# IHM.net
KiCad netlist of a schematic drawn in Altium Designer
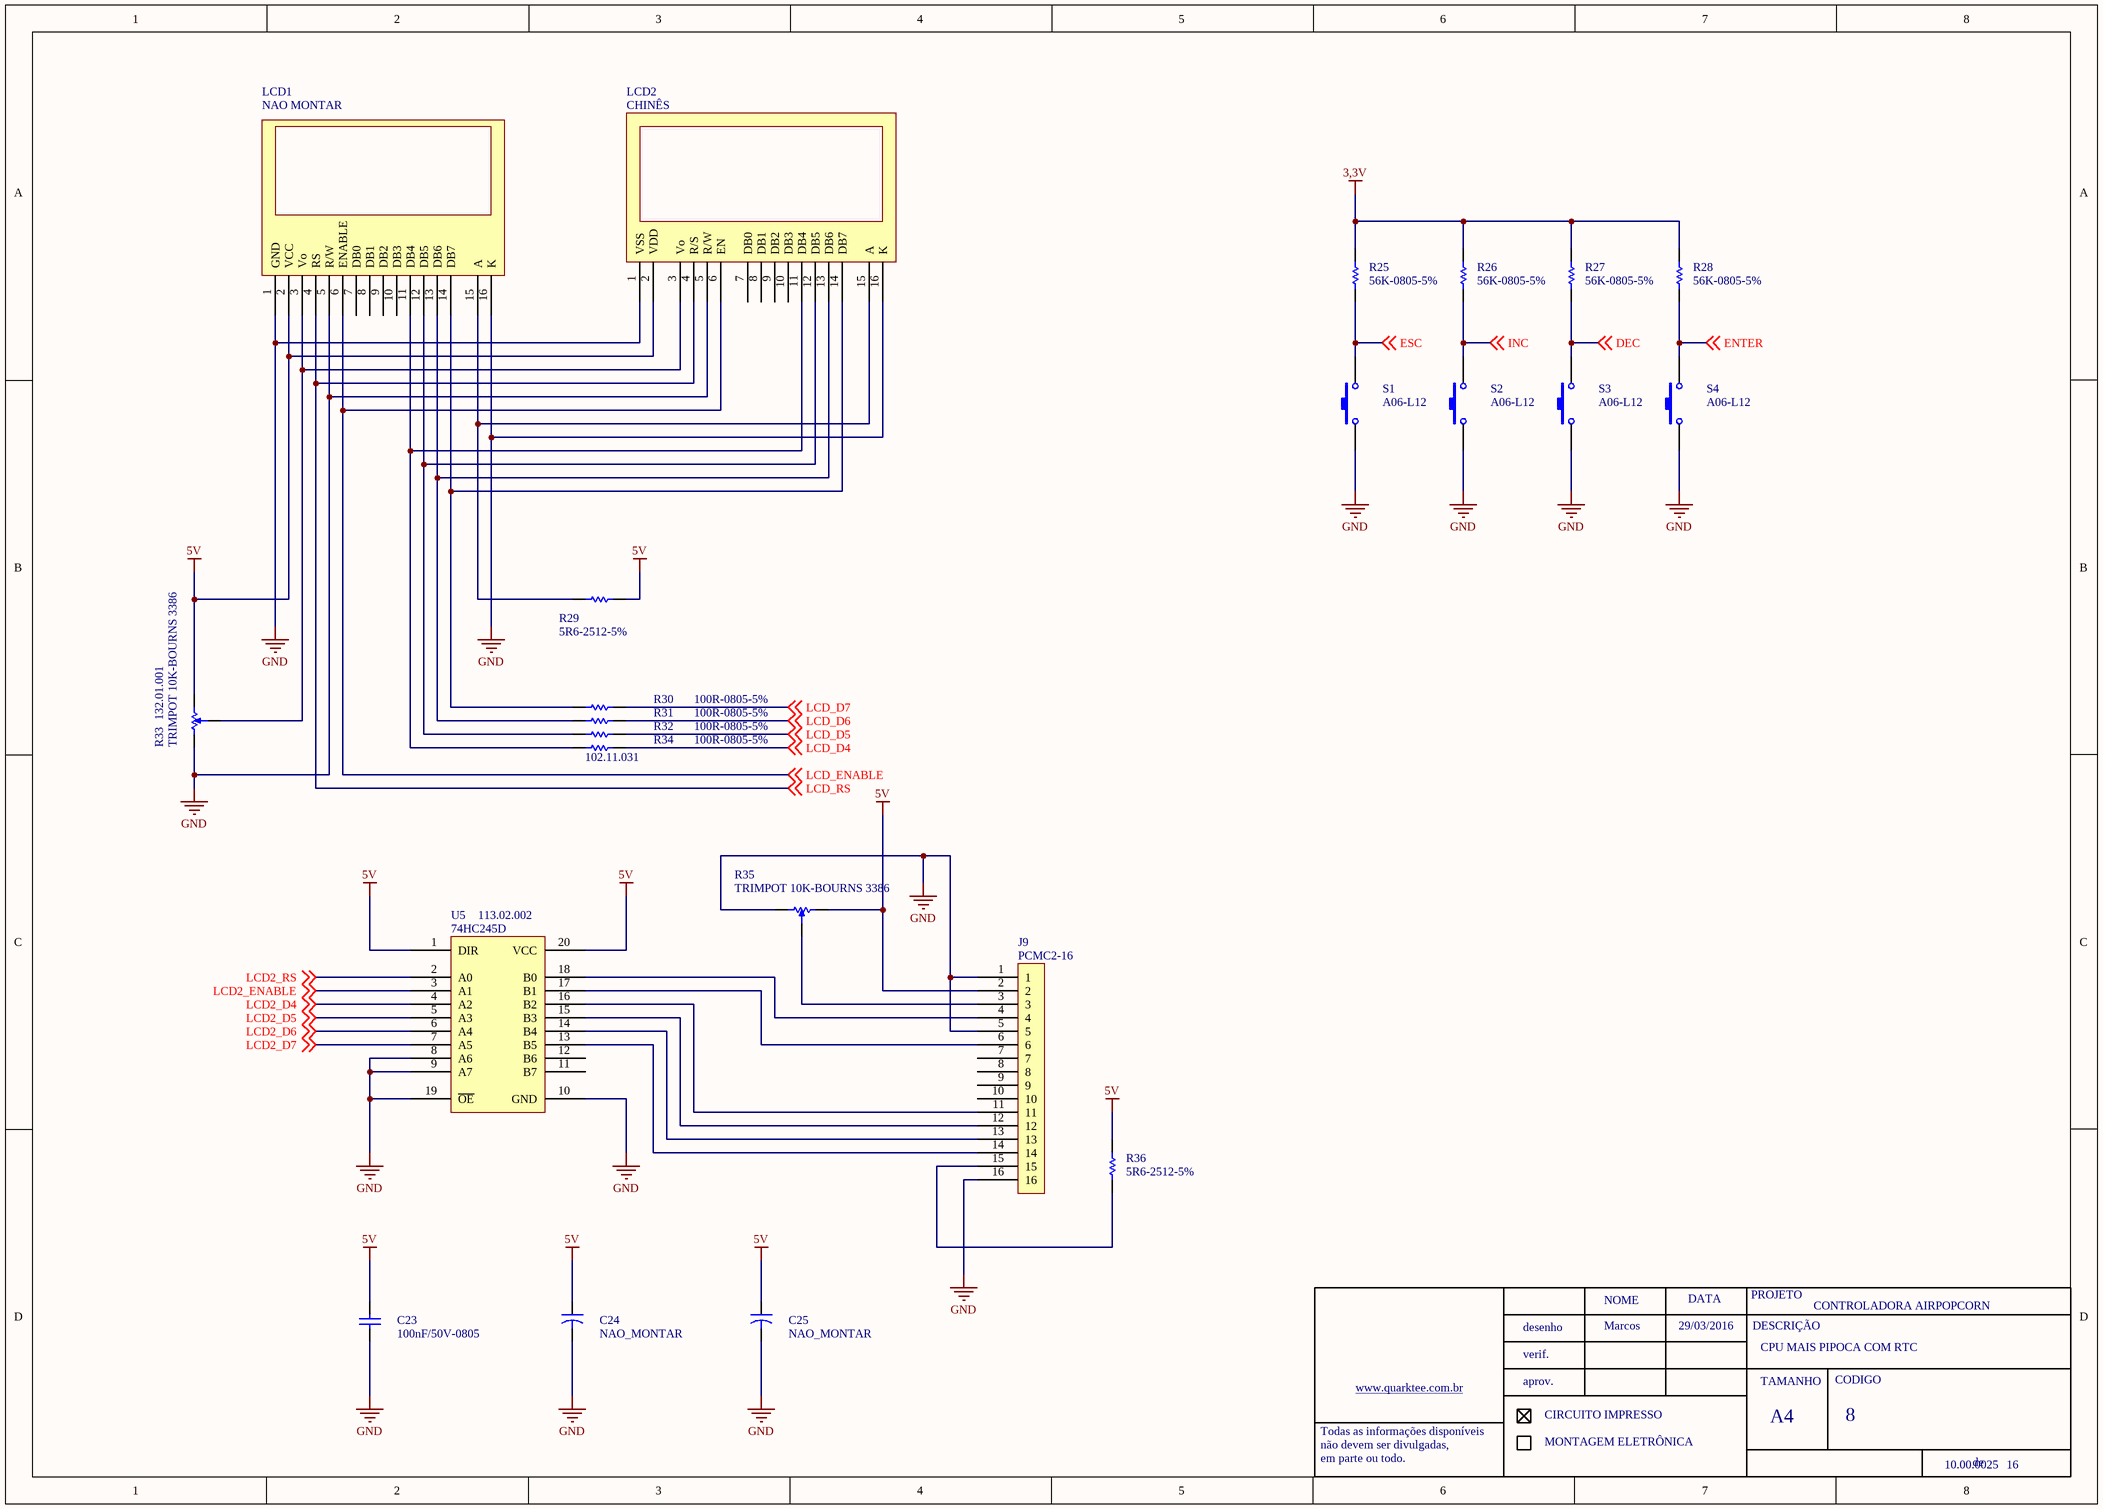
[diagram p0: IHM.SchDoc]

(export (version "E")
  (design (tool "Eeschema 10.0.6"))
  (components
    (comp (ref "C23")
      (value "100nF/50V-0805")
      (footprint "0805-REVISADO O")
      (description "100nF/50-0805-NPO")
      (libsource (lib "AquinoLib") (part "100nF/50-0805-NPO"))
    )
    (comp (ref "C24")
      (value "NAO_MONTAR")
      (footprint "CAP 2413 POLARI")
      (description "10uF/35V-tantalo")
      (libsource (lib "AquinoLib") (part "10uF/35V-tantalo"))
    )
    (comp (ref "C25")
      (value "NAO_MONTAR")
      (footprint "CAP 2413 POLARI")
      (description "10uF/35V-tantalo")
      (libsource (lib "AquinoLib") (part "10uF/35V-tantalo"))
    )
    (comp (ref "J9")
      (value "PCMC2-16")
      (footprint "PCMC2-16")
      (libsource (lib "AquinoLib") (part "PCMC2-16"))
    )
    (comp (ref "LCD1")
      (value "NAO MONTAR")
      (footprint "WH1602_WH1602(Primary)")
      (description "WH1602A")
      (libsource (lib "ChaveDigital3") (part "WH1602A"))
    )
    (comp (ref "LCD2")
      (value "CHINÊS")
      (footprint "LCD CHINES_LCD_CHINES(Primary)")
      (description "WH2002")
      (libsource (lib "ChaveDigital3") (part "WH2002"))
    )
    (comp (ref "R25")
      (value "56K-0805-5%")
      (footprint "0805-REVISADO O")
      (libsource (lib "AquinoLib") (part "56K-0805-5%"))
    )
    (comp (ref "R26")
      (value "56K-0805-5%")
      (footprint "0805-REVISADO O")
      (libsource (lib "AquinoLib") (part "56K-0805-5%"))
    )
    (comp (ref "R27")
      (value "56K-0805-5%")
      (footprint "0805-REVISADO O")
      (libsource (lib "AquinoLib") (part "56K-0805-5%"))
    )
    (comp (ref "R28")
      (value "56K-0805-5%")
      (footprint "0805-REVISADO O")
      (libsource (lib "AquinoLib") (part "56K-0805-5%"))
    )
    (comp (ref "R29")
      (value "5R6-2512-5%")
      (footprint "2512 - REVISADO")
      (description "5R6-CR100")
      (libsource (lib "ChaveDigital3") (part "RES 5R6-CR100"))
    )
    (comp (ref "R30")
      (value "100R-0805-5%")
      (footprint "0805-REVISADO O")
      (libsource (lib "AquinoLib") (part "100R-0805-5%"))
    )
    (comp (ref "R31")
      (value "100R-0805-5%")
      (footprint "0805-REVISADO O")
      (libsource (lib "AquinoLib") (part "100R-0805-5%"))
    )
    (comp (ref "R32")
      (value "100R-0805-5%")
      (footprint "0805-REVISADO O")
      (fields (field (name "ERP") "102.11.031"))
      (libsource (lib "AquinoLib") (part "100R-0805-5%"))
    )
    (comp (ref "R33")
      (value "TRIMPOT 10K-BOURNS 3386")
      (footprint "TRIMPOT 3386")
      (fields (field (name "ERP") "132.01.001"))
      (libsource (lib "ChaveDigital3") (part "TRIMPOT 3386 50K"))
    )
    (comp (ref "R34")
      (value "100R-0805-5%")
      (footprint "0805-REVISADO O")
      (libsource (lib "AquinoLib") (part "100R-0805-5%"))
    )
    (comp (ref "R35")
      (value "TRIMPOT 10K-BOURNS 3386")
      (footprint "TRIMPOT 3386")
      (description "TRIMPOT 100K-0805-5%")
      (libsource (lib "AquinoLib") (part "TRIMPOT 10K-3386"))
    )
    (comp (ref "R36")
      (value "5R6-2512-5%")
      (footprint "2512 - REVISADO")
      (description "5R6-CR100")
      (libsource (lib "ChaveDigital3") (part "RES 5R6-CR100"))
    )
    (comp (ref "S1")
      (value "A06-L12")
      (footprint "CHAVE TACTIL NO_[125](Primary)")
      (libsource (lib "ChaveDigital3") (part "A06-L12"))
    )
    (comp (ref "S2")
      (value "A06-L12")
      (footprint "CHAVE TACTIL NO_[125](Primary)")
      (libsource (lib "ChaveDigital3") (part "A06-L12"))
    )
    (comp (ref "S3")
      (value "A06-L12")
      (footprint "CHAVE TACTIL NO_[125](Primary)")
      (libsource (lib "ChaveDigital3") (part "A06-L12"))
    )
    (comp (ref "S4")
      (value "A06-L12")
      (footprint "CHAVE TACTIL NO_[125](Primary)")
      (libsource (lib "ChaveDigital3") (part "A06-L12"))
    )
    (comp (ref "U5")
      (value "74HC245D")
      (footprint "SOIC 20 FEITO A")
      (fields (field (name "ERP") "113.02.002"))
      (libsource (lib "ChaveDigital3") (part "74HC245D"))
    )
  )
  (nets
    (net (code "1") (name "3,3V") (class "Default")
      (node (ref "R25") (pin "1") (pinfunction "1_1") (pintype "passive"))
      (node (ref "R26") (pin "1") (pinfunction "1_1") (pintype "passive"))
      (node (ref "R27") (pin "1") (pinfunction "1_1") (pintype "passive"))
      (node (ref "R28") (pin "1") (pinfunction "1_1") (pintype "passive"))
    )
    (net (code "2") (name "5V") (class "Default")
      (node (ref "C23") (pin "2") (pinfunction "2_2") (pintype "passive"))
      (node (ref "C24") (pin "1") (pinfunction "1_1") (pintype "passive"))
      (node (ref "C25") (pin "1") (pinfunction "1_1") (pintype "passive"))
      (node (ref "J9") (pin "2") (pinfunction "2_2") (pintype "passive"))
      (node (ref "LCD1") (pin "2") (pinfunction "VCC_2") (pintype "passive"))
      (node (ref "LCD2") (pin "2") (pinfunction "VDD_2") (pintype "passive"))
      (node (ref "R29") (pin "1") (pinfunction "1_1") (pintype "passive"))
      (node (ref "R33") (pin "1") (pinfunction "1_1") (pintype "passive"))
      (node (ref "R35") (pin "1") (pinfunction "1_1") (pintype "passive"))
      (node (ref "R36") (pin "2") (pinfunction "2_2") (pintype "passive"))
      (node (ref "U5") (pin "1") (pinfunction "DIR_1") (pintype "passive"))
      (node (ref "U5") (pin "20") (pinfunction "VCC_20") (pintype "passive"))
    )
    (net (code "3") (name "DEC") (class "Default")
      (node (ref "R27") (pin "2") (pinfunction "2_2") (pintype "passive"))
      (node (ref "S3") (pin "2") (pinfunction "2_2") (pintype "passive"))
    )
    (net (code "4") (name "ENTER") (class "Default")
      (node (ref "R28") (pin "2") (pinfunction "2_2") (pintype "passive"))
      (node (ref "S4") (pin "2") (pinfunction "2_2") (pintype "passive"))
    )
    (net (code "5") (name "ESC") (class "Default")
      (node (ref "R25") (pin "2") (pinfunction "2_2") (pintype "passive"))
      (node (ref "S1") (pin "2") (pinfunction "2_2") (pintype "passive"))
    )
    (net (code "6") (name "GND") (class "Default")
      (node (ref "C23") (pin "1") (pinfunction "1_1") (pintype "passive"))
      (node (ref "C24") (pin "2") (pinfunction "2_2") (pintype "passive"))
      (node (ref "C25") (pin "2") (pinfunction "2_2") (pintype "passive"))
      (node (ref "J9") (pin "1") (pinfunction "1_1") (pintype "passive"))
      (node (ref "J9") (pin "16") (pinfunction "16_16") (pintype "passive"))
      (node (ref "J9") (pin "5") (pinfunction "5_5") (pintype "passive"))
      (node (ref "LCD1") (pin "1") (pinfunction "GND_1") (pintype "passive"))
      (node (ref "LCD1") (pin "16") (pinfunction "K_16") (pintype "passive"))
      (node (ref "LCD1") (pin "5") (pinfunction "R/W_5") (pintype "passive"))
      (node (ref "LCD2") (pin "1") (pinfunction "VSS_1") (pintype "passive"))
      (node (ref "LCD2") (pin "16") (pinfunction "K_16") (pintype "passive"))
      (node (ref "LCD2") (pin "5") (pinfunction "R/W_5") (pintype "passive"))
      (node (ref "R33") (pin "3") (pinfunction "3_3") (pintype "passive"))
      (node (ref "R35") (pin "3") (pinfunction "3_3") (pintype "passive"))
      (node (ref "S1") (pin "1") (pinfunction "1_1") (pintype "passive"))
      (node (ref "S2") (pin "1") (pinfunction "1_1") (pintype "passive"))
      (node (ref "S3") (pin "1") (pinfunction "1_1") (pintype "passive"))
      (node (ref "S4") (pin "1") (pinfunction "1_1") (pintype "passive"))
      (node (ref "U5") (pin "10") (pinfunction "GND_10") (pintype "passive"))
      (node (ref "U5") (pin "19") (pinfunction "~{OE}_19") (pintype "passive"))
      (node (ref "U5") (pin "8") (pinfunction "A6_8") (pintype "passive"))
      (node (ref "U5") (pin "9") (pinfunction "A7_9") (pintype "passive"))
    )
    (net (code "7") (name "INC") (class "Default")
      (node (ref "R26") (pin "2") (pinfunction "2_2") (pintype "passive"))
      (node (ref "S2") (pin "2") (pinfunction "2_2") (pintype "passive"))
    )
    (net (code "8") (name "LCD2_D4") (class "Default")
      (node (ref "U5") (pin "4") (pinfunction "A2_4") (pintype "passive"))
    )
    (net (code "9") (name "LCD2_D5") (class "Default")
      (node (ref "U5") (pin "5") (pinfunction "A3_5") (pintype "passive"))
    )
    (net (code "10") (name "LCD2_D6") (class "Default")
      (node (ref "U5") (pin "6") (pinfunction "A4_6") (pintype "passive"))
    )
    (net (code "11") (name "LCD2_D7") (class "Default")
      (node (ref "U5") (pin "7") (pinfunction "A5_7") (pintype "passive"))
    )
    (net (code "12") (name "LCD2_ENABLE") (class "Default")
      (node (ref "U5") (pin "3") (pinfunction "A1_3") (pintype "passive"))
    )
    (net (code "13") (name "LCD2_RS") (class "Default")
      (node (ref "U5") (pin "2") (pinfunction "A0_2") (pintype "passive"))
    )
    (net (code "14") (name "LCD_D4") (class "Default")
      (node (ref "R34") (pin "2") (pinfunction "2_2") (pintype "passive"))
    )
    (net (code "15") (name "LCD_D5") (class "Default")
      (node (ref "R32") (pin "2") (pinfunction "2_2") (pintype "passive"))
    )
    (net (code "16") (name "LCD_D6") (class "Default")
      (node (ref "R31") (pin "2") (pinfunction "2_2") (pintype "passive"))
    )
    (net (code "17") (name "LCD_D7") (class "Default")
      (node (ref "R30") (pin "2") (pinfunction "2_2") (pintype "passive"))
    )
    (net (code "18") (name "LCD_ENABLE") (class "Default")
      (node (ref "LCD1") (pin "6") (pinfunction "ENABLE_6") (pintype "passive"))
      (node (ref "LCD2") (pin "6") (pinfunction "EN_6") (pintype "passive"))
    )
    (net (code "19") (name "LCD_RS") (class "Default")
      (node (ref "LCD1") (pin "4") (pinfunction "RS_4") (pintype "passive"))
      (node (ref "LCD2") (pin "4") (pinfunction "R/S_4") (pintype "passive"))
    )
    (net (code "20") (name "Net-(J9-Pad3)") (class "Default")
      (node (ref "J9") (pin "3") (pinfunction "3_3") (pintype "passive"))
      (node (ref "R35") (pin "2") (pinfunction "2_2") (pintype "passive"))
    )
    (net (code "21") (name "Net-(J9-Pad15)") (class "Default")
      (node (ref "J9") (pin "15") (pinfunction "15_15") (pintype "passive"))
      (node (ref "R36") (pin "1") (pinfunction "1_1") (pintype "passive"))
    )
    (net (code "22") (name "Net-(LCD1-A)") (class "Default")
      (node (ref "LCD1") (pin "15") (pinfunction "A_15") (pintype "passive"))
      (node (ref "LCD2") (pin "15") (pinfunction "A_15") (pintype "passive"))
      (node (ref "R29") (pin "2") (pinfunction "2_2") (pintype "passive"))
    )
    (net (code "23") (name "Net-(LCD1-DB4)") (class "Default")
      (node (ref "LCD1") (pin "11") (pinfunction "DB4_11") (pintype "passive"))
      (node (ref "LCD2") (pin "11") (pinfunction "DB4_11") (pintype "passive"))
      (node (ref "R34") (pin "1") (pinfunction "1_1") (pintype "passive"))
    )
    (net (code "24") (name "Net-(LCD1-DB5)") (class "Default")
      (node (ref "LCD1") (pin "12") (pinfunction "DB5_12") (pintype "passive"))
      (node (ref "LCD2") (pin "12") (pinfunction "DB5_12") (pintype "passive"))
      (node (ref "R32") (pin "1") (pinfunction "1_1") (pintype "passive"))
    )
    (net (code "25") (name "Net-(LCD1-DB6)") (class "Default")
      (node (ref "LCD1") (pin "13") (pinfunction "DB6_13") (pintype "passive"))
      (node (ref "LCD2") (pin "13") (pinfunction "DB6_13") (pintype "passive"))
      (node (ref "R31") (pin "1") (pinfunction "1_1") (pintype "passive"))
    )
    (net (code "26") (name "Net-(LCD1-DB7)") (class "Default")
      (node (ref "LCD1") (pin "14") (pinfunction "DB7_14") (pintype "passive"))
      (node (ref "LCD2") (pin "14") (pinfunction "DB7_14") (pintype "passive"))
      (node (ref "R30") (pin "1") (pinfunction "1_1") (pintype "passive"))
    )
    (net (code "27") (name "Net-(LCD1-Vo)") (class "Default")
      (node (ref "LCD1") (pin "3") (pinfunction "Vo_3") (pintype "passive"))
      (node (ref "LCD2") (pin "3") (pinfunction "Vo_3") (pintype "passive"))
      (node (ref "R33") (pin "2") (pinfunction "2_2") (pintype "passive"))
    )
    (net (code "28") (name "Net-(U5-B0)") (class "Default")
      (node (ref "J9") (pin "4") (pinfunction "4_4") (pintype "passive"))
      (node (ref "U5") (pin "18") (pinfunction "B0_18") (pintype "passive"))
    )
    (net (code "29") (name "Net-(U5-B1)") (class "Default")
      (node (ref "J9") (pin "6") (pinfunction "6_6") (pintype "passive"))
      (node (ref "U5") (pin "17") (pinfunction "B1_17") (pintype "passive"))
    )
    (net (code "30") (name "Net-(U5-B2)") (class "Default")
      (node (ref "J9") (pin "11") (pinfunction "11_11") (pintype "passive"))
      (node (ref "U5") (pin "16") (pinfunction "B2_16") (pintype "passive"))
    )
    (net (code "31") (name "Net-(U5-B3)") (class "Default")
      (node (ref "J9") (pin "12") (pinfunction "12_12") (pintype "passive"))
      (node (ref "U5") (pin "15") (pinfunction "B3_15") (pintype "passive"))
    )
    (net (code "32") (name "Net-(U5-B4)") (class "Default")
      (node (ref "J9") (pin "13") (pinfunction "13_13") (pintype "passive"))
      (node (ref "U5") (pin "14") (pinfunction "B4_14") (pintype "passive"))
    )
    (net (code "33") (name "Net-(U5-B5)") (class "Default")
      (node (ref "J9") (pin "14") (pinfunction "14_14") (pintype "passive"))
      (node (ref "U5") (pin "13") (pinfunction "B5_13") (pintype "passive"))
    )
    (net (code "34") (name "unconnected-(J9-Pad7)") (class "Default")
      (node (ref "J9") (pin "7") (pinfunction "7_7") (pintype "passive"))
    )
    (net (code "35") (name "unconnected-(J9-Pad8)") (class "Default")
      (node (ref "J9") (pin "8") (pinfunction "8_8") (pintype "passive"))
    )
    (net (code "36") (name "unconnected-(J9-Pad9)") (class "Default")
      (node (ref "J9") (pin "9") (pinfunction "9_9") (pintype "passive"))
    )
    (net (code "37") (name "unconnected-(J9-Pad10)") (class "Default")
      (node (ref "J9") (pin "10") (pinfunction "10_10") (pintype "passive"))
    )
    (net (code "38") (name "unconnected-(LCD1-DB0-Pad7)") (class "Default")
      (node (ref "LCD1") (pin "7") (pinfunction "DB0_7") (pintype "passive"))
    )
    (net (code "39") (name "unconnected-(LCD1-DB1-Pad8)") (class "Default")
      (node (ref "LCD1") (pin "8") (pinfunction "DB1_8") (pintype "passive"))
    )
    (net (code "40") (name "unconnected-(LCD1-DB2-Pad9)") (class "Default")
      (node (ref "LCD1") (pin "9") (pinfunction "DB2_9") (pintype "passive"))
    )
    (net (code "41") (name "unconnected-(LCD1-DB3-Pad10)") (class "Default")
      (node (ref "LCD1") (pin "10") (pinfunction "DB3_10") (pintype "passive"))
    )
    (net (code "42") (name "unconnected-(LCD2-DB0-Pad7)") (class "Default")
      (node (ref "LCD2") (pin "7") (pinfunction "DB0_7") (pintype "passive"))
    )
    (net (code "43") (name "unconnected-(LCD2-DB1-Pad8)") (class "Default")
      (node (ref "LCD2") (pin "8") (pinfunction "DB1_8") (pintype "passive"))
    )
    (net (code "44") (name "unconnected-(LCD2-DB2-Pad9)") (class "Default")
      (node (ref "LCD2") (pin "9") (pinfunction "DB2_9") (pintype "passive"))
    )
    (net (code "45") (name "unconnected-(LCD2-DB3-Pad10)") (class "Default")
      (node (ref "LCD2") (pin "10") (pinfunction "DB3_10") (pintype "passive"))
    )
    (net (code "46") (name "unconnected-(U5-B6-Pad12)") (class "Default")
      (node (ref "U5") (pin "12") (pinfunction "B6_12") (pintype "passive"))
    )
    (net (code "47") (name "unconnected-(U5-B7-Pad11)") (class "Default")
      (node (ref "U5") (pin "11") (pinfunction "B7_11") (pintype "passive"))
    )
  )
)
